# GPIO.net
KiCad netlist of a schematic drawn in Altium Designer
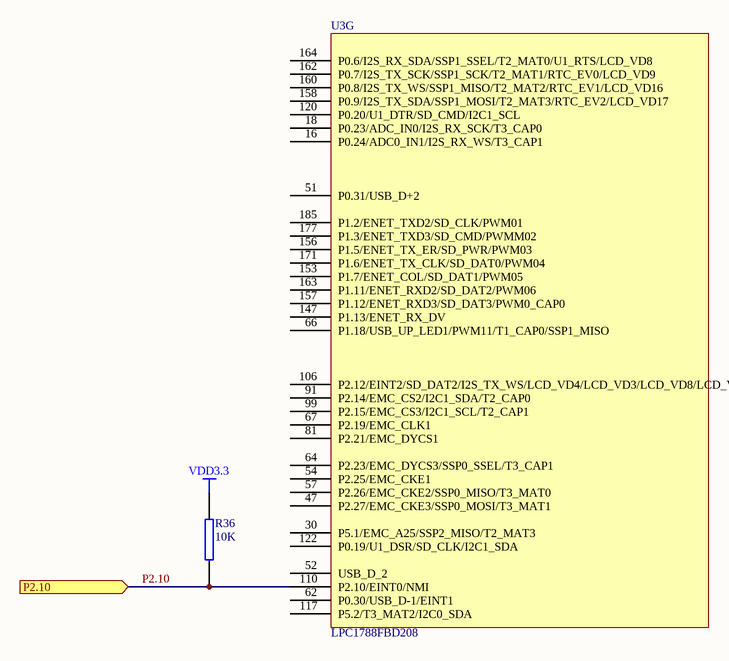
[diagram p0: GPIO.SchDoc]

(export (version "E")
  (design (tool "Eeschema 10.0.6"))
  (components
    (comp (ref "R36") (value "10K") (footprint "R0603") (libsource (lib "*") (part "RES2")))
    (comp (ref "U3")
      (value "LPC1788FBD208")
      (footprint "QFP208")
      (libsource (lib "LPC1788") (part "LPC1788FBD208"))
    )
  )
  (nets
    (net (code "1") (name "/P2.10") (class "Default")
      (node (ref "R36") (pin "1") (pinfunction "1_1") (pintype "passive"))
      (node (ref "U3") (pin "110") (pinfunction "P2.10/EINT0/NMI_110") (pintype "passive"))
    )
    (net (code "2") (name "VDD3.3") (class "Default")
      (node (ref "R36") (pin "2") (pinfunction "2_2") (pintype "passive"))
    )
    (net (code "3") (name "unconnected-(U3G-P0.6{slash}I2S_RX_SDA{slash}SSP1_SSEL{slash}T2_MAT0{slash}U1_RTS{slash}LCD_VD8-Pad164)") (class "Default")
      (node (ref "U3") (pin "164") (pinfunction "P0.6/I2S_RX_SDA/SSP1_SSEL/T2_MAT0/U1_RTS/LCD_VD8_164") (pintype "passive"))
    )
    (net (code "4") (name "unconnected-(U3G-P0.7{slash}I2S_TX_SCK{slash}SSP1_SCK{slash}T2_MAT1{slash}RTC_EV0{slash}LCD_VD9-Pad162)") (class "Default")
      (node (ref "U3") (pin "162") (pinfunction "P0.7/I2S_TX_SCK/SSP1_SCK/T2_MAT1/RTC_EV0/LCD_VD9_162") (pintype "passive"))
    )
    (net (code "5") (name "unconnected-(U3G-P0.8{slash}I2S_TX_WS{slash}SSP1_MISO{slash}T2_MAT2{slash}RTC_EV1{slash}LCD_VD16-Pad160)") (class "Default")
      (node (ref "U3") (pin "160") (pinfunction "P0.8/I2S_TX_WS/SSP1_MISO/T2_MAT2/RTC_EV1/LCD_VD16_160") (pintype "passive"))
    )
    (net (code "6") (name "unconnected-(U3G-P0.9{slash}I2S_TX_SDA{slash}SSP1_MOSI{slash}T2_MAT3{slash}RTC_EV2{slash}LCD_VD17-Pad158)") (class "Default")
      (node (ref "U3") (pin "158") (pinfunction "P0.9/I2S_TX_SDA/SSP1_MOSI/T2_MAT3/RTC_EV2/LCD_VD17_158") (pintype "passive"))
    )
    (net (code "7") (name "unconnected-(U3G-P0.19{slash}U1_DSR{slash}SD_CLK{slash}I2C1_SDA-Pad122)") (class "Default")
      (node (ref "U3") (pin "122") (pinfunction "P0.19/U1_DSR/SD_CLK/I2C1_SDA_122") (pintype "passive"))
    )
    (net (code "8") (name "unconnected-(U3G-P0.20{slash}U1_DTR{slash}SD_CMD{slash}I2C1_SCL-Pad120)") (class "Default")
      (node (ref "U3") (pin "120") (pinfunction "P0.20/U1_DTR/SD_CMD/I2C1_SCL_120") (pintype "passive"))
    )
    (net (code "9") (name "unconnected-(U3G-P0.23{slash}ADC_IN0{slash}I2S_RX_SCK{slash}T3_CAP0-Pad18)") (class "Default")
      (node (ref "U3") (pin "18") (pinfunction "P0.23/ADC_IN0/I2S_RX_SCK/T3_CAP0_18") (pintype "passive"))
    )
    (net (code "10") (name "unconnected-(U3G-P0.24{slash}ADC0_IN1{slash}I2S_RX_WS{slash}T3_CAP1-Pad16)") (class "Default")
      (node (ref "U3") (pin "16") (pinfunction "P0.24/ADC0_IN1/I2S_RX_WS/T3_CAP1_16") (pintype "passive"))
    )
    (net (code "11") (name "unconnected-(U3G-P0.30{slash}USB_D-1{slash}EINT1-Pad62)") (class "Default")
      (node (ref "U3") (pin "62") (pinfunction "P0.30/USB_D-1/EINT1_62") (pintype "passive"))
    )
    (net (code "12") (name "unconnected-(U3G-P0.31{slash}USB_D+2-Pad51)") (class "Default")
      (node (ref "U3") (pin "51") (pinfunction "P0.31/USB_D+2_51") (pintype "passive"))
    )
    (net (code "13") (name "unconnected-(U3G-P1.2{slash}ENET_TXD2{slash}SD_CLK{slash}PWM01-Pad185)") (class "Default")
      (node (ref "U3") (pin "185") (pinfunction "P1.2/ENET_TXD2/SD_CLK/PWM01_185") (pintype "passive"))
    )
    (net (code "14") (name "unconnected-(U3G-P1.3{slash}ENET_TXD3{slash}SD_CMD{slash}PWMM02-Pad177)") (class "Default")
      (node (ref "U3") (pin "177") (pinfunction "P1.3/ENET_TXD3/SD_CMD/PWMM02_177") (pintype "passive"))
    )
    (net (code "15") (name "unconnected-(U3G-P1.5{slash}ENET_TX_ER{slash}SD_PWR{slash}PWM03-Pad156)") (class "Default")
      (node (ref "U3") (pin "156") (pinfunction "P1.5/ENET_TX_ER/SD_PWR/PWM03_156") (pintype "passive"))
    )
    (net (code "16") (name "unconnected-(U3G-P1.6{slash}ENET_TX_CLK{slash}SD_DAT0{slash}PWM04-Pad171)") (class "Default")
      (node (ref "U3") (pin "171") (pinfunction "P1.6/ENET_TX_CLK/SD_DAT0/PWM04_171") (pintype "passive"))
    )
    (net (code "17") (name "unconnected-(U3G-P1.7{slash}ENET_COL{slash}SD_DAT1{slash}PWM05-Pad153)") (class "Default")
      (node (ref "U3") (pin "153") (pinfunction "P1.7/ENET_COL/SD_DAT1/PWM05_153") (pintype "passive"))
    )
    (net (code "18") (name "unconnected-(U3G-P1.11{slash}ENET_RXD2{slash}SD_DAT2{slash}PWM06-Pad163)") (class "Default")
      (node (ref "U3") (pin "163") (pinfunction "P1.11/ENET_RXD2/SD_DAT2/PWM06_163") (pintype "passive"))
    )
    (net (code "19") (name "unconnected-(U3G-P1.12{slash}ENET_RXD3{slash}SD_DAT3{slash}PWM0_CAP0-Pad157)") (class "Default")
      (node (ref "U3") (pin "157") (pinfunction "P1.12/ENET_RXD3/SD_DAT3/PWM0_CAP0_157") (pintype "passive"))
    )
    (net (code "20") (name "unconnected-(U3G-P1.13{slash}ENET_RX_DV-Pad147)") (class "Default")
      (node (ref "U3") (pin "147") (pinfunction "P1.13/ENET_RX_DV_147") (pintype "passive"))
    )
    (net (code "21") (name "unconnected-(U3G-P1.18{slash}USB_UP_LED1{slash}PWM11{slash}T1_CAP0{slash}SSP1_MISO-Pad66)") (class "Default")
      (node (ref "U3") (pin "66") (pinfunction "P1.18/USB_UP_LED1/PWM11/T1_CAP0/SSP1_MISO_66") (pintype "passive"))
    )
    (net (code "22") (name "unconnected-(U3G-P2.12{slash}EINT2{slash}SD_DAT2{slash}I2S_TX_WS{slash}LCD_VD4{slash}LCD_VD3{slash}LCD_VD8{slash}LCD_VD18-Pad106)") (class "Default")
      (node (ref "U3") (pin "106") (pinfunction "P2.12/EINT2/SD_DAT2/I2S_TX_WS/LCD_VD4/LCD_VD3/LCD_VD8/LCD_VD18_106") (pintype "passive"))
    )
    (net (code "23") (name "unconnected-(U3G-P2.14{slash}EMC_CS2{slash}I2C1_SDA{slash}T2_CAP0-Pad91)") (class "Default")
      (node (ref "U3") (pin "91") (pinfunction "P2.14/EMC_CS2/I2C1_SDA/T2_CAP0_91") (pintype "passive"))
    )
    (net (code "24") (name "unconnected-(U3G-P2.15{slash}EMC_CS3{slash}I2C1_SCL{slash}T2_CAP1-Pad99)") (class "Default")
      (node (ref "U3") (pin "99") (pinfunction "P2.15/EMC_CS3/I2C1_SCL/T2_CAP1_99") (pintype "passive"))
    )
    (net (code "25") (name "unconnected-(U3G-P2.19{slash}EMC_CLK1-Pad67)") (class "Default")
      (node (ref "U3") (pin "67") (pinfunction "P2.19/EMC_CLK1_67") (pintype "passive"))
    )
    (net (code "26") (name "unconnected-(U3G-P2.21{slash}EMC_DYCS1-Pad81)") (class "Default")
      (node (ref "U3") (pin "81") (pinfunction "P2.21/EMC_DYCS1_81") (pintype "passive"))
    )
    (net (code "27") (name "unconnected-(U3G-P2.23{slash}EMC_DYCS3{slash}SSP0_SSEL{slash}T3_CAP1-Pad64)") (class "Default")
      (node (ref "U3") (pin "64") (pinfunction "P2.23/EMC_DYCS3/SSP0_SSEL/T3_CAP1_64") (pintype "passive"))
    )
    (net (code "28") (name "unconnected-(U3G-P2.25{slash}EMC_CKE1-Pad54)") (class "Default")
      (node (ref "U3") (pin "54") (pinfunction "P2.25/EMC_CKE1_54") (pintype "passive"))
    )
    (net (code "29") (name "unconnected-(U3G-P2.26{slash}EMC_CKE2{slash}SSP0_MISO{slash}T3_MAT0-Pad57)") (class "Default")
      (node (ref "U3") (pin "57") (pinfunction "P2.26/EMC_CKE2/SSP0_MISO/T3_MAT0_57") (pintype "passive"))
    )
    (net (code "30") (name "unconnected-(U3G-P2.27{slash}EMC_CKE3{slash}SSP0_MOSI{slash}T3_MAT1-Pad47)") (class "Default")
      (node (ref "U3") (pin "47") (pinfunction "P2.27/EMC_CKE3/SSP0_MOSI/T3_MAT1_47") (pintype "passive"))
    )
    (net (code "31") (name "unconnected-(U3G-P5.1{slash}EMC_A25{slash}SSP2_MISO{slash}T2_MAT3-Pad30)") (class "Default")
      (node (ref "U3") (pin "30") (pinfunction "P5.1/EMC_A25/SSP2_MISO/T2_MAT3_30") (pintype "passive"))
    )
    (net (code "32") (name "unconnected-(U3G-P5.2{slash}T3_MAT2{slash}I2C0_SDA-Pad117)") (class "Default")
      (node (ref "U3") (pin "117") (pinfunction "P5.2/T3_MAT2/I2C0_SDA_117") (pintype "passive"))
    )
    (net (code "33") (name "unconnected-(U3G-USB_D_2-Pad52)") (class "Default")
      (node (ref "U3") (pin "52") (pinfunction "USB_D_2_52") (pintype "passive"))
    )
  )
)
